# PSU_BZX84C7V5_-7V5.net
KiCad netlist of a schematic drawn in Altium Designer
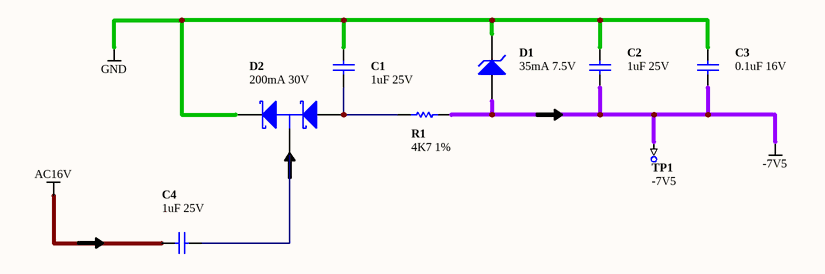
[diagram p0: PSU_BZX84C7V5_-7V5.SchDoc]

(export (version "E")
  (design (tool "Eeschema 10.0.6"))
  (components
    (comp (ref "C1")
      (value "1uF 25V")
      (footprint "CAPC3216-STAR")
      (description "Capacitor, Ceramic, 1uF 10% 25V 1206 (3216) X7R")
      (fields (field (name "TOLERANCE") "10 %"))
      (libsource (lib "altium-import") (part "root_2_CAP-NP_"))
    )
    (comp (ref "C2")
      (value "1uF 25V")
      (footprint "CAPC3216-STAR")
      (description "Capacitor, Ceramic, 1uF 10% 25V 1206 (3216) X7R")
      (fields (field (name "TOLERANCE") "10 %"))
      (libsource (lib "altium-import") (part "root_2_CAP-NP_"))
    )
    (comp (ref "C3")
      (value "0.1uF 16V")
      (footprint "CAPC1005-STAR")
      (description "Capacitor, Ceramic, 0.1uF 10% 16V 0402 (1005) X7R")
      (fields (field (name "TOLERANCE") "10 %"))
      (libsource (lib "altium-import") (part "root_0_CAP-NP_"))
    )
    (comp (ref "C4")
      (value "1uF 25V")
      (footprint "CAPC3216-STAR")
      (description "Capacitor, Ceramic, 1uF 10% 25V 1206 (3216) X7R")
      (fields (field (name "TOLERANCE") "10 %"))
      (libsource (lib "altium-import") (part "root_1_CAP-NP_"))
    )
    (comp (ref "D1")
      (value "35mA 7.5V")
      (footprint "SOT95P230-3D")
      (description "Zener Diode, 7.5V 35mA")
      (libsource (lib "altium-import") (part "root_1_DIO-ZENER-1-3_"))
    )
    (comp (ref "D2")
      (value "200mA 30V")
      (footprint "SOT95P230-3C")
      (description "Schottky Diode, Dual-Serial, BAT54S 30V 200mA")
      (libsource (lib "altium-import") (part "root_2_DIO-SCHOTTKY-2S_"))
    )
    (comp (ref "R1")
      (value "4K7 1%")
      (footprint "RESC1005-STAR")
      (description "Resistor, 4K7 1% 0402 (1005)")
      (fields (field (name "TOLERANCE") "1 %"))
      (libsource (lib "altium-import") (part "root_1_RES_"))
    )
    (comp (ref "TP1")
      (value "-7V5")
      (footprint "TestPin")
      (description "Test Point, PCB Mount with Silkscreen Box")
      (libsource (lib "AltiumDesignLibrary") (part "TestPin"))
    )
  )
  (nets
    (net (code "1") (name "-7V5") (class "Default")
      (node (ref "C2") (pin "1") (pinfunction "1_1") (pintype "passive"))
      (node (ref "C3") (pin "2") (pinfunction "2_2") (pintype "passive"))
      (node (ref "D1") (pin "1") (pinfunction "A_1") (pintype "passive"))
      (node (ref "R1") (pin "2") (pinfunction "2_2") (pintype "passive"))
      (node (ref "TP1") (pin "1") (pinfunction "1_1") (pintype "input"))
    )
    (net (code "2") (name "AC16V") (class "Default")
      (node (ref "C4") (pin "1") (pinfunction "1_1") (pintype "passive"))
    )
    (net (code "3") (name "GND") (class "Default")
      (node (ref "C1") (pin "2") (pinfunction "2_2") (pintype "passive"))
      (node (ref "C2") (pin "2") (pinfunction "2_2") (pintype "passive"))
      (node (ref "C3") (pin "1") (pinfunction "1_1") (pintype "passive"))
      (node (ref "D1") (pin "2") (pinfunction "K_2") (pintype "passive"))
      (node (ref "D2") (pin "2") (pinfunction "K_2") (pintype "passive"))
    )
    (net (code "4") (name "Net-(D2-A)") (class "Default")
      (node (ref "C1") (pin "1") (pinfunction "1_1") (pintype "passive"))
      (node (ref "D2") (pin "1") (pinfunction "A_1") (pintype "passive"))
      (node (ref "R1") (pin "1") (pinfunction "1_1") (pintype "passive"))
    )
    (net (code "5") (name "Net-(D2-C)") (class "Default")
      (node (ref "C4") (pin "2") (pinfunction "2_2") (pintype "passive"))
      (node (ref "D2") (pin "3") (pinfunction "C_3") (pintype "passive"))
    )
  )
)
